# design.net
KiCad netlist of a schematic drawn in Altium Designer
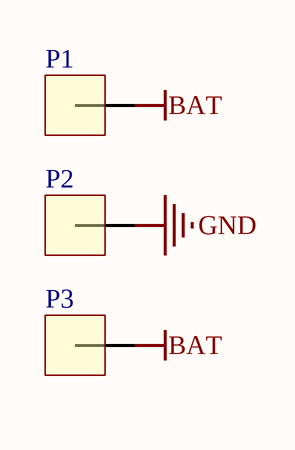
[diagram p0: 电子脚铐本体电池转接板.SchDoc]

(export (version "E")
  (design (tool "Eeschema 10.0.6"))
  (components
    (comp (ref "P1")
      (value "~")
      (footprint "Pad3.2*3.2*7.1-SM")
      (description "Pad-1.5x1-1")
      (libsource (lib "MhSchlib") (part "Pad-1.5x1-1"))
    )
    (comp (ref "P2")
      (value "~")
      (footprint "Pad3.2*3.2*7.1-SM")
      (description "Pad-1.5x1-1")
      (libsource (lib "MhSchlib") (part "Pad-1.5x1-1"))
    )
    (comp (ref "P3")
      (value "~")
      (footprint "Pad3.2*3.2*7.1-SM")
      (description "Pad-1.5x1-1")
      (libsource (lib "MhSchlib") (part "Pad-1.5x1-1"))
    )
  )
  (nets
    (net (code "1") (name "BAT") (class "Default")
      (node (ref "P1") (pin "1") (pinfunction "1_1") (pintype "passive"))
      (node (ref "P3") (pin "1") (pinfunction "1_1") (pintype "passive"))
    )
    (net (code "2") (name "GND") (class "Default")
      (node (ref "P2") (pin "1") (pinfunction "1_1") (pintype "passive"))
    )
  )
)
